# LPC812_breakout_v2_2.net
KiCad netlist of a schematic drawn in EAGLE
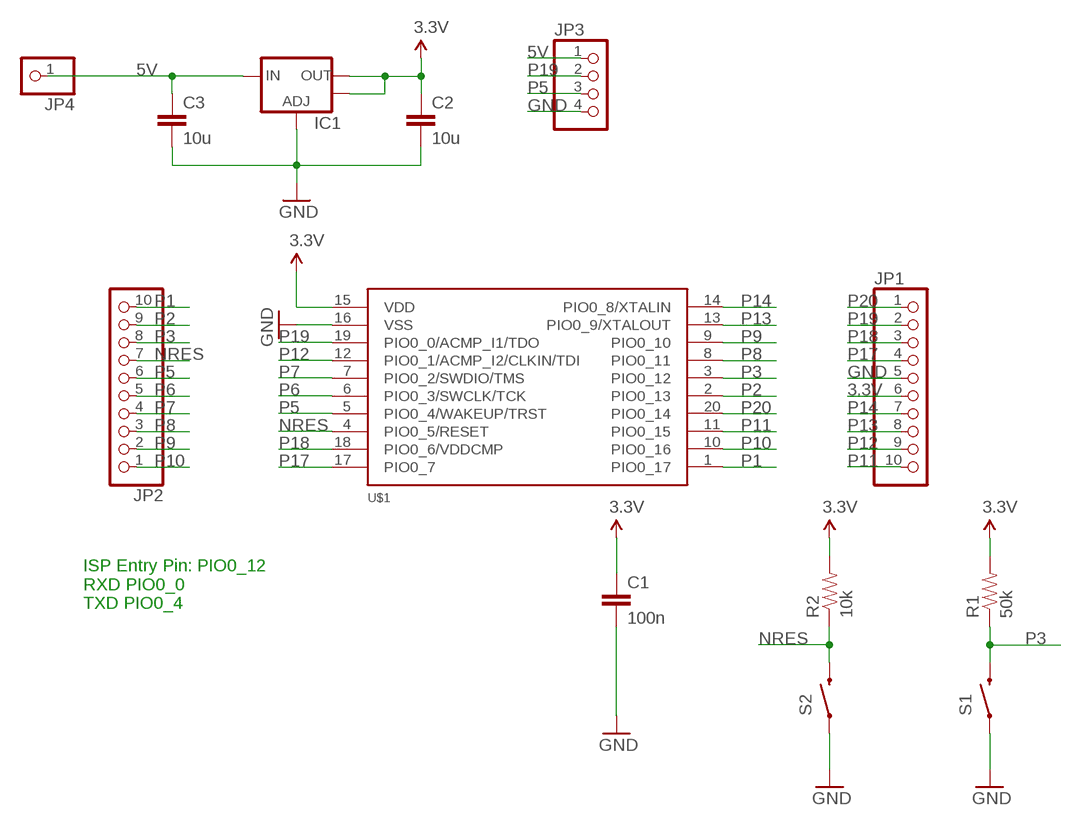
[diagram p0: schematic, sheet 1]

(export (version "E")
  (design (tool "Eeschema 10.0.6"))
  (components
    (comp (ref "C1")
      (value "100n")
      (footprint "eagle-import:0805")
      (libsource (lib "eagle-import") (part "CAP0805"))
    )
    (comp (ref "C2")
      (value "10u")
      (footprint "eagle-import:0805")
      (libsource (lib "eagle-import") (part "CAP0805"))
    )
    (comp (ref "C3")
      (value "10u")
      (footprint "eagle-import:0805")
      (libsource (lib "eagle-import") (part "CAP0805"))
    )
    (comp (ref "IC1")
      (value "V_REG_LM1117SOT223")
      (footprint "eagle-import:SOT223")
      (libsource (lib "eagle-import") (part "V_REG_LM1117SOT223"))
    )
    (comp (ref "JP1")
      (value "HEADER-1X10ROUND")
      (footprint "eagle-import:1X10_ROUND")
      (libsource (lib "eagle-import") (part "HEADER-1X10ROUND"))
    )
    (comp (ref "JP2")
      (value "HEADER-1X10ROUND")
      (footprint "eagle-import:1X10_ROUND")
      (libsource (lib "eagle-import") (part "HEADER-1X10ROUND"))
    )
    (comp (ref "JP3")
      (value "HEADER-1X4ROUND")
      (footprint "eagle-import:1X04_ROUND")
      (libsource (lib "eagle-import") (part "HEADER-1X4ROUND"))
    )
    (comp (ref "JP4")
      (value "HEADER-1X1ROUND")
      (footprint "eagle-import:1X01_ROUND")
      (libsource (lib "eagle-import") (part "HEADER-1X1ROUND"))
    )
    (comp (ref "R1")
      (value "50k")
      (footprint "eagle-import:0805")
      (libsource (lib "eagle-import") (part "RESISTOR0805-RES"))
    )
    (comp (ref "R2")
      (value "10k")
      (footprint "eagle-import:0805")
      (libsource (lib "eagle-import") (part "RESISTOR0805-RES"))
    )
    (comp (ref "S1")
      (value "SWITCH-MOMENTARY-2-SMD-1101NE")
      (footprint "eagle-import:TACTILE-SWITCH-1101NE")
      (libsource (lib "eagle-import") (part "SWITCH-MOMENTARY-2-SMD-1101NE"))
    )
    (comp (ref "S2")
      (value "SWITCH-MOMENTARY-2-SMD-1101NE")
      (footprint "eagle-import:TACTILE-SWITCH-1101NE")
      (libsource (lib "eagle-import") (part "SWITCH-MOMENTARY-2-SMD-1101NE"))
    )
    (comp (ref "U$1")
      (value "LPC812M101JDH20")
      (footprint "eagle-import:TSSOP20")
      (libsource (lib "eagle-import") (part "LPC812M101JDH20"))
    )
  )
  (nets
    (net (code "1") (name "/5V") (class "Default")
      (node (ref "C3") (pin "1") (pinfunction "1_1") (pintype "passive"))
      (node (ref "IC1") (pin "3") (pinfunction "IN_3") (pintype "input"))
      (node (ref "JP3") (pin "1") (pinfunction "1_1") (pintype "passive"))
      (node (ref "JP4") (pin "1") (pinfunction "1_1") (pintype "passive"))
    )
    (net (code "2") (name "/NRES") (class "Default")
      (node (ref "JP2") (pin "7") (pinfunction "7_7") (pintype "passive"))
      (node (ref "R2") (pin "1") (pinfunction "1_1") (pintype "passive"))
      (node (ref "S2") (pin "P$2") (pinfunction "2_P$2") (pintype "passive"))
      (node (ref "U$1") (pin "4") (pinfunction "PIO0_5/RESET_4") (pintype "bidirectional"))
    )
    (net (code "3") (name "/P1") (class "Default")
      (node (ref "JP2") (pin "10") (pinfunction "10_10") (pintype "passive"))
      (node (ref "U$1") (pin "1") (pinfunction "PIO0_17_1") (pintype "bidirectional"))
    )
    (net (code "4") (name "/P2") (class "Default")
      (node (ref "JP2") (pin "9") (pinfunction "9_9") (pintype "passive"))
      (node (ref "U$1") (pin "2") (pinfunction "PIO0_13_2") (pintype "bidirectional"))
    )
    (net (code "5") (name "/P3") (class "Default")
      (node (ref "JP2") (pin "8") (pinfunction "8_8") (pintype "passive"))
      (node (ref "R1") (pin "1") (pinfunction "1_1") (pintype "passive"))
      (node (ref "S1") (pin "P$2") (pinfunction "2_P$2") (pintype "passive"))
      (node (ref "U$1") (pin "3") (pinfunction "PIO0_12_3") (pintype "bidirectional"))
    )
    (net (code "6") (name "/P5") (class "Default")
      (node (ref "JP2") (pin "6") (pinfunction "6_6") (pintype "passive"))
      (node (ref "JP3") (pin "3") (pinfunction "3_3") (pintype "passive"))
      (node (ref "U$1") (pin "5") (pinfunction "PIO0_4/WAKEUP/TRST_5") (pintype "bidirectional"))
    )
    (net (code "7") (name "/P6") (class "Default")
      (node (ref "JP2") (pin "5") (pinfunction "5_5") (pintype "passive"))
      (node (ref "U$1") (pin "6") (pinfunction "PIO0_3/SWCLK/TCK_6") (pintype "bidirectional"))
    )
    (net (code "8") (name "/P7") (class "Default")
      (node (ref "JP2") (pin "4") (pinfunction "4_4") (pintype "passive"))
      (node (ref "U$1") (pin "7") (pinfunction "PIO0_2/SWDIO/TMS_7") (pintype "bidirectional"))
    )
    (net (code "9") (name "/P8") (class "Default")
      (node (ref "JP2") (pin "3") (pinfunction "3_3") (pintype "passive"))
      (node (ref "U$1") (pin "8") (pinfunction "PIO0_11_8") (pintype "bidirectional"))
    )
    (net (code "10") (name "/P9") (class "Default")
      (node (ref "JP2") (pin "2") (pinfunction "2_2") (pintype "passive"))
      (node (ref "U$1") (pin "9") (pinfunction "PIO0_10_9") (pintype "bidirectional"))
    )
    (net (code "11") (name "/P10") (class "Default")
      (node (ref "JP2") (pin "1") (pinfunction "1_1") (pintype "passive"))
      (node (ref "U$1") (pin "10") (pinfunction "PIO0_16_10") (pintype "bidirectional"))
    )
    (net (code "12") (name "/P11") (class "Default")
      (node (ref "JP1") (pin "10") (pinfunction "10_10") (pintype "passive"))
      (node (ref "U$1") (pin "11") (pinfunction "PIO0_15_11") (pintype "bidirectional"))
    )
    (net (code "13") (name "/P12") (class "Default")
      (node (ref "JP1") (pin "9") (pinfunction "9_9") (pintype "passive"))
      (node (ref "U$1") (pin "12") (pinfunction "PIO0_1/ACMP_I2/CLKIN/TDI_12") (pintype "bidirectional"))
    )
    (net (code "14") (name "/P13") (class "Default")
      (node (ref "JP1") (pin "8") (pinfunction "8_8") (pintype "passive"))
      (node (ref "U$1") (pin "13") (pinfunction "PIO0_9/XTALOUT_13") (pintype "bidirectional"))
    )
    (net (code "15") (name "/P14") (class "Default")
      (node (ref "JP1") (pin "7") (pinfunction "7_7") (pintype "passive"))
      (node (ref "U$1") (pin "14") (pinfunction "PIO0_8/XTALIN_14") (pintype "bidirectional"))
    )
    (net (code "16") (name "/P17") (class "Default")
      (node (ref "JP1") (pin "4") (pinfunction "4_4") (pintype "passive"))
      (node (ref "U$1") (pin "17") (pinfunction "PIO0_7_17") (pintype "bidirectional"))
    )
    (net (code "17") (name "/P18") (class "Default")
      (node (ref "JP1") (pin "3") (pinfunction "3_3") (pintype "passive"))
      (node (ref "U$1") (pin "18") (pinfunction "PIO0_6/VDDCMP_18") (pintype "bidirectional"))
    )
    (net (code "18") (name "/P19") (class "Default")
      (node (ref "JP1") (pin "2") (pinfunction "2_2") (pintype "passive"))
      (node (ref "JP3") (pin "2") (pinfunction "2_2") (pintype "passive"))
      (node (ref "U$1") (pin "19") (pinfunction "PIO0_0/ACMP_I1/TDO_19") (pintype "bidirectional"))
    )
    (net (code "19") (name "/P20") (class "Default")
      (node (ref "JP1") (pin "1") (pinfunction "1_1") (pintype "passive"))
      (node (ref "U$1") (pin "20") (pinfunction "PIO0_14_20") (pintype "bidirectional"))
    )
    (net (code "20") (name "3.3V") (class "Default")
      (node (ref "C1") (pin "1") (pinfunction "1_1") (pintype "passive"))
      (node (ref "C2") (pin "1") (pinfunction "1_1") (pintype "passive"))
      (node (ref "IC1") (pin "2") (pinfunction "OUT_2") (pintype "output"))
      (node (ref "IC1") (pin "4") (pinfunction "OUT_4") (pintype "output"))
      (node (ref "JP1") (pin "6") (pinfunction "6_6") (pintype "passive"))
      (node (ref "R1") (pin "2") (pinfunction "2_2") (pintype "passive"))
      (node (ref "R2") (pin "2") (pinfunction "2_2") (pintype "passive"))
      (node (ref "U$1") (pin "15") (pinfunction "VDD_15") (pintype "bidirectional"))
    )
    (net (code "21") (name "GND") (class "Default")
      (node (ref "C1") (pin "2") (pinfunction "2_2") (pintype "passive"))
      (node (ref "C2") (pin "2") (pinfunction "2_2") (pintype "passive"))
      (node (ref "C3") (pin "2") (pinfunction "2_2") (pintype "passive"))
      (node (ref "IC1") (pin "1") (pinfunction "ADJ_1") (pintype "input"))
      (node (ref "JP1") (pin "5") (pinfunction "5_5") (pintype "passive"))
      (node (ref "JP3") (pin "4") (pinfunction "4_4") (pintype "passive"))
      (node (ref "S1") (pin "P$1") (pinfunction "1_P$1") (pintype "passive"))
      (node (ref "S2") (pin "P$1") (pinfunction "1_P$1") (pintype "passive"))
      (node (ref "U$1") (pin "16") (pinfunction "VSS_16") (pintype "bidirectional"))
    )
  )
)
